# BW0253_LEVEL_SHIFT.net
KiCad netlist of a schematic drawn in Altium Designer
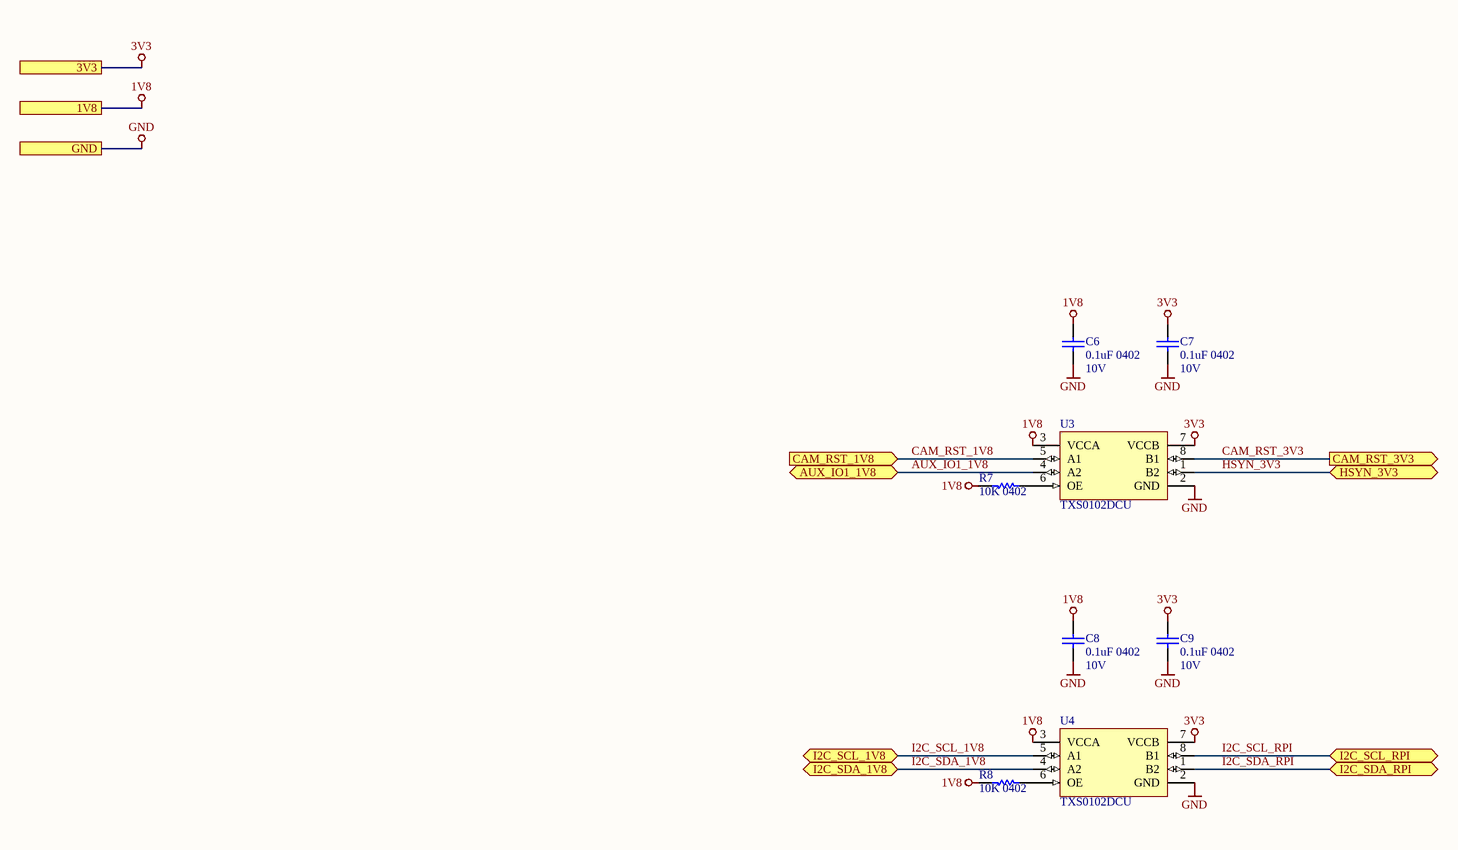
[diagram p0: BW0253_LEVEL_SHIFT.SchDoc]

(export (version "E")
  (design (tool "Eeschema 10.0.6"))
  (components
    (comp (ref "C6")
      (value "0.1uF 0402")
      (footprint "CAP_Altium_Vault_Generic:CAPC0402(1005)70_N")
      (description "CAP CER 0.1UF 10V X7R 0402 5%")
      (fields (field (name "TOLERANCE") "5%") (field (name "VOLTAGE RATING") "10V"))
      (libsource (lib "LuxonisMaster") (part "GRM155R71A104JA01D"))
    )
    (comp (ref "C7")
      (value "0.1uF 0402")
      (footprint "CAP_Altium_Vault_Generic:CAPC0402(1005)70_N")
      (description "CAP CER 0.1UF 10V X7R 0402 5%")
      (fields (field (name "TOLERANCE") "5%") (field (name "VOLTAGE RATING") "10V"))
      (libsource (lib "LuxonisMaster") (part "GRM155R71A104JA01D"))
    )
    (comp (ref "C8")
      (value "0.1uF 0402")
      (footprint "CAP_Altium_Vault_Generic:CAPC0402(1005)70_N")
      (description "CAP CER 0.1UF 10V X7R 0402 5%")
      (fields (field (name "TOLERANCE") "5%") (field (name "VOLTAGE RATING") "10V"))
      (libsource (lib "LuxonisMaster") (part "GRM155R71A104JA01D"))
    )
    (comp (ref "C9")
      (value "0.1uF 0402")
      (footprint "CAP_Altium_Vault_Generic:CAPC0402(1005)70_N")
      (description "CAP CER 0.1UF 10V X7R 0402 5%")
      (fields (field (name "TOLERANCE") "5%") (field (name "VOLTAGE RATING") "10V"))
      (libsource (lib "LuxonisMaster") (part "GRM155R71A104JA01D"))
    )
    (comp (ref "R7")
      (value "10K 0402")
      (footprint "RES_Altium_Vault_Generic:RESC0402(1005)_N")
      (fields (field (name "TOLERANCE") "1%"))
      (libsource (lib "LuxonisMaster") (part "RC0402FR-1310KL"))
    )
    (comp (ref "R8")
      (value "10K 0402")
      (footprint "RES_Altium_Vault_Generic:RESC0402(1005)_N")
      (fields (field (name "TOLERANCE") "1%"))
      (libsource (lib "LuxonisMaster") (part "RC0402FR-1310KL"))
    )
    (comp (ref "U3")
      (value "TXS0102DCU")
      (footprint "LuxonisMaster:TXS0102DCUR")
      (description "TEXAS INSTRUMENTS - TXS0102DCUR - IC, TRANSLATOR, 2 BIT, BI, US-8")
      (libsource (lib "LuxonisMaster") (part "TXS0102DCUR"))
    )
    (comp (ref "U4")
      (value "TXS0102DCU")
      (footprint "LuxonisMaster:TXS0102DCUR")
      (description "TEXAS INSTRUMENTS - TXS0102DCUR - IC, TRANSLATOR, 2 BIT, BI, US-8")
      (libsource (lib "LuxonisMaster") (part "TXS0102DCUR"))
    )
  )
  (nets
    (net (code "1") (name "/AUX_IO1_1V8") (class "Default")
      (node (ref "U3") (pin "4") (pinfunction "A2_4") (pintype "bidirectional"))
    )
    (net (code "2") (name "/CAM_RST_1V8") (class "Default")
      (node (ref "U3") (pin "5") (pinfunction "A1_5") (pintype "bidirectional"))
    )
    (net (code "3") (name "/CAM_RST_3V3") (class "Default")
      (node (ref "U3") (pin "8") (pinfunction "B1_8") (pintype "bidirectional"))
    )
    (net (code "4") (name "/HSYN_3V3") (class "Default")
      (node (ref "U3") (pin "1") (pinfunction "B2_1") (pintype "bidirectional"))
    )
    (net (code "5") (name "/I2C_SCL_1V8") (class "Default")
      (node (ref "U4") (pin "5") (pinfunction "A1_5") (pintype "bidirectional"))
    )
    (net (code "6") (name "/I2C_SCL_RPI") (class "Default")
      (node (ref "U4") (pin "8") (pinfunction "B1_8") (pintype "bidirectional"))
    )
    (net (code "7") (name "/I2C_SDA_1V8") (class "Default")
      (node (ref "U4") (pin "4") (pinfunction "A2_4") (pintype "bidirectional"))
    )
    (net (code "8") (name "/I2C_SDA_RPI") (class "Default")
      (node (ref "U4") (pin "1") (pinfunction "B2_1") (pintype "bidirectional"))
    )
    (net (code "9") (name "1V8") (class "Default")
      (node (ref "C6") (pin "2") (pinfunction "2_2") (pintype "passive"))
      (node (ref "C8") (pin "2") (pinfunction "2_2") (pintype "passive"))
      (node (ref "R7") (pin "2") (pinfunction "2_2") (pintype "passive"))
      (node (ref "R8") (pin "2") (pinfunction "2_2") (pintype "passive"))
      (node (ref "U3") (pin "3") (pinfunction "VCCA_3") (pintype "power_in"))
      (node (ref "U4") (pin "3") (pinfunction "VCCA_3") (pintype "power_in"))
    )
    (net (code "10") (name "3V3") (class "Default")
      (node (ref "C7") (pin "2") (pinfunction "2_2") (pintype "passive"))
      (node (ref "C9") (pin "2") (pinfunction "2_2") (pintype "passive"))
      (node (ref "U3") (pin "7") (pinfunction "VCCB_7") (pintype "power_in"))
      (node (ref "U4") (pin "7") (pinfunction "VCCB_7") (pintype "power_in"))
    )
    (net (code "11") (name "GND") (class "Default")
      (node (ref "C6") (pin "1") (pinfunction "1_1") (pintype "passive"))
      (node (ref "C7") (pin "1") (pinfunction "1_1") (pintype "passive"))
      (node (ref "C8") (pin "1") (pinfunction "1_1") (pintype "passive"))
      (node (ref "C9") (pin "1") (pinfunction "1_1") (pintype "passive"))
      (node (ref "U3") (pin "2") (pinfunction "GND_2") (pintype "power_in"))
      (node (ref "U4") (pin "2") (pinfunction "GND_2") (pintype "power_in"))
    )
    (net (code "12") (name "Net-(U3-OE)") (class "Default")
      (node (ref "R7") (pin "1") (pinfunction "1_1") (pintype "passive"))
      (node (ref "U3") (pin "6") (pinfunction "OE_6") (pintype "input"))
    )
    (net (code "13") (name "Net-(U4-OE)") (class "Default")
      (node (ref "R8") (pin "1") (pinfunction "1_1") (pintype "passive"))
      (node (ref "U4") (pin "6") (pinfunction "OE_6") (pintype "input"))
    )
  )
)
